# Connections.net
KiCad netlist of a schematic drawn in Altium Designer
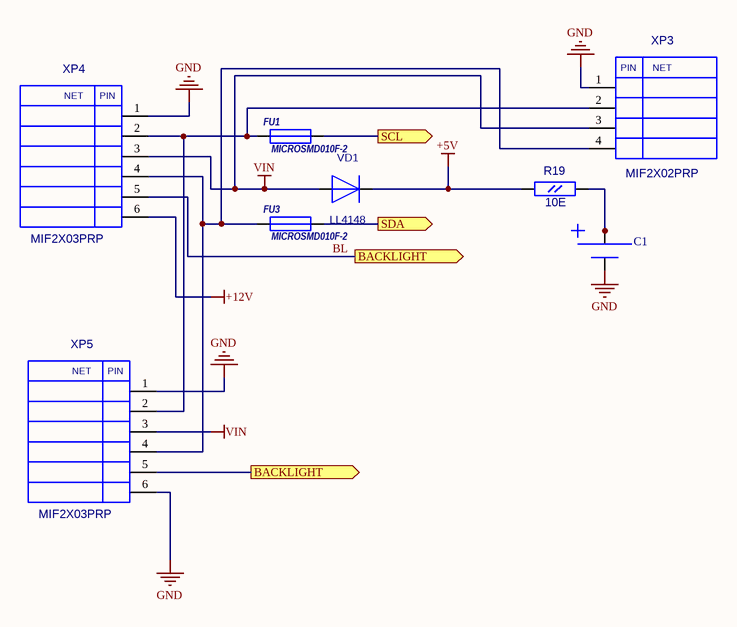
[diagram p0: Connections.SchDoc]

(export (version "E")
  (design (tool "Eeschema 10.0.6"))
  (components
    (comp (ref "C1")
      (value "EEC-S5R5H105")
      (footprint "CR2032_ONBOARD")
      (libsource (lib "gprs_modem_2") (part "CR2032-VBY2"))
    )
    (comp (ref "FU1")
      (value "MICROSMD010F-2")
      (footprint "RC1210")
      (description "MICROSMD")
      (libsource (lib "gprs_modem_2") (part "MICROSMD"))
    )
    (comp (ref "FU3")
      (value "MICROSMD010F-2")
      (footprint "RC1210")
      (description "MICROSMD")
      (libsource (lib "gprs_modem_2") (part "MICROSMD"))
    )
    (comp (ref "R19")
      (value "10E")
      (footprint "RC0603")
      (description "RC0603")
      (libsource (lib "gprs_modem_2") (part "RC0603"))
    )
    (comp (ref "VD1") (value "LL4148") (footprint "SOD-80") (libsource (lib "gprs_modem_2") (part "LL4148")))
    (comp (ref "XP3")
      (value "MIF2X02PRP")
      (footprint "MIF2X02PRP")
      (libsource (lib "gprs_modem_2") (part "MIF2X02PRP"))
    )
    (comp (ref "XP4")
      (value "MIF2X03PRP")
      (footprint "MIF2X03PRP")
      (libsource (lib "gprs_modem_2") (part "MIF2X03PRP"))
    )
    (comp (ref "XP5")
      (value "MIF2X03PRP")
      (footprint "MIF2X03PRP")
      (libsource (lib "gprs_modem_2") (part "MIF2X03PRP"))
    )
  )
  (nets
    (net (code "1") (name "+5V") (class "Default")
      (node (ref "R19") (pin "1") (pinfunction "A_1") (pintype "passive"))
      (node (ref "VD1") (pin "2") (pinfunction "+_2") (pintype "passive"))
    )
    (net (code "2") (name "+12V") (class "Default")
      (node (ref "XP4") (pin "6") (pinfunction "6_6") (pintype "passive"))
    )
    (net (code "3") (name "/BL") (class "Default")
      (node (ref "XP4") (pin "5") (pinfunction "5_5") (pintype "passive"))
      (node (ref "XP5") (pin "5") (pinfunction "5_5") (pintype "passive"))
    )
    (net (code "4") (name "/SCL") (class "Default") (node (ref "FU1") (pin "2") (pintype "passive")))
    (net (code "5") (name "/SDA") (class "Default") (node (ref "FU3") (pin "2") (pintype "passive")))
    (net (code "6") (name "GND") (class "Default")
      (node (ref "C1") (pin "1") (pintype "passive"))
      (node (ref "XP3") (pin "1") (pinfunction "1_1") (pintype "passive"))
      (node (ref "XP4") (pin "1") (pinfunction "1_1") (pintype "passive"))
      (node (ref "XP5") (pin "1") (pinfunction "1_1") (pintype "passive"))
      (node (ref "XP5") (pin "6") (pinfunction "6_6") (pintype "passive"))
    )
    (net (code "7") (name "Net-(FU1-Pad1)") (class "Default")
      (node (ref "FU1") (pin "1") (pintype "passive"))
      (node (ref "XP3") (pin "2") (pinfunction "2_2") (pintype "passive"))
      (node (ref "XP4") (pin "2") (pinfunction "2_2") (pintype "passive"))
      (node (ref "XP5") (pin "2") (pinfunction "2_2") (pintype "passive"))
    )
    (net (code "8") (name "Net-(FU3-Pad1)") (class "Default")
      (node (ref "FU3") (pin "1") (pintype "passive"))
      (node (ref "XP3") (pin "4") (pinfunction "4_4") (pintype "passive"))
      (node (ref "XP4") (pin "4") (pinfunction "4_4") (pintype "passive"))
      (node (ref "XP5") (pin "4") (pinfunction "4_4") (pintype "passive"))
    )
    (net (code "9") (name "Net-(R19-B)") (class "Default")
      (node (ref "C1") (pin "2") (pintype "passive"))
      (node (ref "C1") (pin "3") (pintype "passive"))
      (node (ref "C1") (pin "4") (pintype "passive"))
      (node (ref "R19") (pin "2") (pinfunction "B_2") (pintype "passive"))
    )
    (net (code "10") (name "VIN") (class "Default")
      (node (ref "VD1") (pin "1") (pinfunction "-_1") (pintype "passive"))
      (node (ref "XP3") (pin "3") (pinfunction "3_3") (pintype "passive"))
      (node (ref "XP4") (pin "3") (pinfunction "3_3") (pintype "passive"))
      (node (ref "XP5") (pin "3") (pinfunction "3_3") (pintype "passive"))
    )
  )
)
